# tm8_chinese.net
KiCad netlist of a schematic drawn in EAGLE
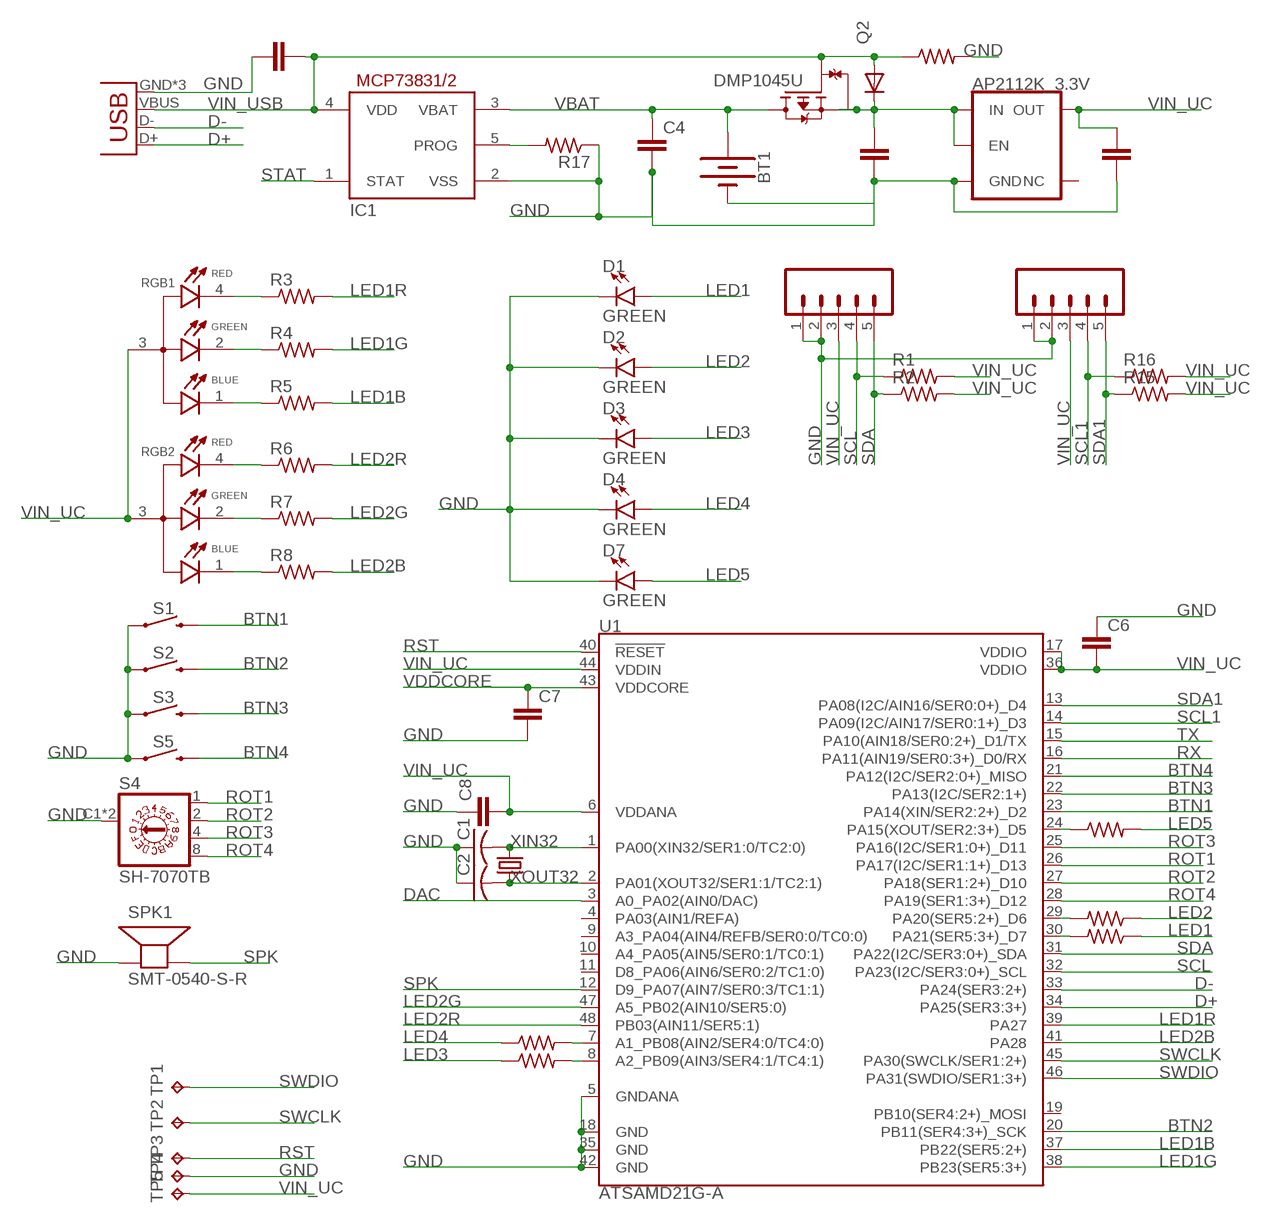
[diagram p0: schematic, sheet 1]

(export (version "E")
  (design (tool "Eeschema 10.0.6"))
  (components
    (comp (ref "AP2112K_3.3V")
      (value "3.3V")
      (footprint "eagle-import:SOT23-5")
      (libsource (lib "eagle-import") (part "V_REG_AP2112K-3.3V"))
    )
    (comp (ref "BT1")
      (value "BATTERY-20MM_SMD_4LEGS_OVERPASTE_INNER")
      (footprint "eagle-import:BATTCON_20MM_4LEGS_OVERPASTE_INNER")
      (libsource (lib "eagle-import") (part "BATTERY-20MM_SMD_4LEGS_OVERPASTE_INNER"))
    )
    (comp (ref "C1")
      (value "C-USC0603")
      (footprint "eagle-import:C0603")
      (libsource (lib "eagle-import") (part "C-USC0603"))
    )
    (comp (ref "C2")
      (value "C-USC0603")
      (footprint "eagle-import:C0603")
      (libsource (lib "eagle-import") (part "C-USC0603"))
    )
    (comp (ref "C3")
      (value "C-EUC0603")
      (footprint "eagle-import:C0603")
      (libsource (lib "eagle-import") (part "C-EUC0603"))
    )
    (comp (ref "C4")
      (value "C-EUC0603")
      (footprint "eagle-import:C0603")
      (libsource (lib "eagle-import") (part "C-EUC0603"))
    )
    (comp (ref "C5")
      (value "C-EUC0603")
      (footprint "eagle-import:C0603")
      (libsource (lib "eagle-import") (part "C-EUC0603"))
    )
    (comp (ref "C6")
      (value "C-EUC0603")
      (footprint "eagle-import:C0603")
      (libsource (lib "eagle-import") (part "C-EUC0603"))
    )
    (comp (ref "C7")
      (value "C-EUC0603")
      (footprint "eagle-import:C0603")
      (libsource (lib "eagle-import") (part "C-EUC0603"))
    )
    (comp (ref "C8")
      (value "C-EUC0603")
      (footprint "eagle-import:C0603")
      (libsource (lib "eagle-import") (part "C-EUC0603"))
    )
    (comp (ref "C9")
      (value "C-EUC0603")
      (footprint "eagle-import:C0603")
      (libsource (lib "eagle-import") (part "C-EUC0603"))
    )
    (comp (ref "D1")
      (value "GREEN")
      (footprint "eagle-import:LED-1206")
      (libsource (lib "eagle-import") (part "LED-GREEN1206"))
    )
    (comp (ref "D2")
      (value "GREEN")
      (footprint "eagle-import:LED-1206")
      (libsource (lib "eagle-import") (part "LED-GREEN1206"))
    )
    (comp (ref "D3")
      (value "GREEN")
      (footprint "eagle-import:LED-1206")
      (libsource (lib "eagle-import") (part "LED-GREEN1206"))
    )
    (comp (ref "D4")
      (value "GREEN")
      (footprint "eagle-import:LED-1206")
      (libsource (lib "eagle-import") (part "LED-GREEN1206"))
    )
    (comp (ref "D7")
      (value "GREEN")
      (footprint "eagle-import:LED-1206")
      (libsource (lib "eagle-import") (part "LED-GREEN1206"))
    )
    (comp (ref "D8")
      (value "DIODESOD-323F")
      (footprint "eagle-import:SOD-323F")
      (libsource (lib "eagle-import") (part "DIODESOD-323F"))
    )
    (comp (ref "IC1")
      (value "MCP73831/OT")
      (footprint "eagle-import:SOT23-5L")
      (libsource (lib "eagle-import") (part "MCP73831/OT"))
    )
    (comp (ref "JP2")
      (value "USB-MICROB")
      (footprint "eagle-import:USB-MICROB")
      (libsource (lib "eagle-import") (part "USB-MICROB"))
    )
    (comp (ref "LCD1")
      (value "CONN_05VERT_FEMALE_HEADER")
      (footprint "eagle-import:1X05_SMD_VERTICAL_COMBO")
      (libsource (lib "eagle-import") (part "CONN_05VERT_FEMALE_HEADER"))
    )
    (comp (ref "LCD2")
      (value "CONN_05VERT_FEMALE_HEADER")
      (footprint "eagle-import:1X05_SMD_VERTICAL_COMBO")
      (libsource (lib "eagle-import") (part "CONN_05VERT_FEMALE_HEADER"))
    )
    (comp (ref "Q2")
      (value "DMP1045U")
      (footprint "eagle-import:SOT91P240X110-3N")
      (fields (field (name "MF") "Diodes Inc."))
      (libsource (lib "eagle-import") (part "DMP1045U"))
    )
    (comp (ref "R1")
      (value "R-US_R0603")
      (footprint "eagle-import:R0603")
      (libsource (lib "eagle-import") (part "rcl_334_R-US_R0603"))
    )
    (comp (ref "R2")
      (value "R-US_R0603")
      (footprint "eagle-import:R0603")
      (libsource (lib "eagle-import") (part "rcl_334_R-US_R0603"))
    )
    (comp (ref "R3")
      (value "R-US_R0603")
      (footprint "eagle-import:R0603")
      (libsource (lib "eagle-import") (part "rcl_334_R-US_R0603"))
    )
    (comp (ref "R4")
      (value "R-US_R0603")
      (footprint "eagle-import:R0603")
      (libsource (lib "eagle-import") (part "rcl_334_R-US_R0603"))
    )
    (comp (ref "R5")
      (value "R-US_R0603")
      (footprint "eagle-import:R0603")
      (libsource (lib "eagle-import") (part "rcl_334_R-US_R0603"))
    )
    (comp (ref "R6")
      (value "R-US_R0603")
      (footprint "eagle-import:R0603")
      (libsource (lib "eagle-import") (part "rcl_334_R-US_R0603"))
    )
    (comp (ref "R7")
      (value "R-US_R0603")
      (footprint "eagle-import:R0603")
      (libsource (lib "eagle-import") (part "rcl_334_R-US_R0603"))
    )
    (comp (ref "R8")
      (value "R-US_R0603")
      (footprint "eagle-import:R0603")
      (libsource (lib "eagle-import") (part "rcl_334_R-US_R0603"))
    )
    (comp (ref "R9")
      (value "R-US_R0603")
      (footprint "eagle-import:R0603")
      (libsource (lib "eagle-import") (part "rcl_334_R-US_R0603"))
    )
    (comp (ref "R10")
      (value "R-US_R0603")
      (footprint "eagle-import:R0603")
      (libsource (lib "eagle-import") (part "rcl_334_R-US_R0603"))
    )
    (comp (ref "R11")
      (value "R-US_R0603")
      (footprint "eagle-import:R0603")
      (libsource (lib "eagle-import") (part "rcl_334_R-US_R0603"))
    )
    (comp (ref "R12")
      (value "R-US_R0603")
      (footprint "eagle-import:R0603")
      (libsource (lib "eagle-import") (part "rcl_334_R-US_R0603"))
    )
    (comp (ref "R13")
      (value "R-US_R0603")
      (footprint "eagle-import:R0603")
      (libsource (lib "eagle-import") (part "rcl_334_R-US_R0603"))
    )
    (comp (ref "R14")
      (value "R-US_R0603")
      (footprint "eagle-import:R0603")
      (libsource (lib "eagle-import") (part "R-US_R0603"))
    )
    (comp (ref "R15")
      (value "R-US_R0603")
      (footprint "eagle-import:R0603")
      (libsource (lib "eagle-import") (part "rcl_334_R-US_R0603"))
    )
    (comp (ref "R16")
      (value "R-US_R0603")
      (footprint "eagle-import:R0603")
      (libsource (lib "eagle-import") (part "rcl_334_R-US_R0603"))
    )
    (comp (ref "R17")
      (value "R-US_R0603")
      (footprint "eagle-import:R0603")
      (libsource (lib "eagle-import") (part "adafruit_25768682_R-US_R0603"))
    )
    (comp (ref "RGB1")
      (value "EAST1616RGBA3")
      (footprint "eagle-import:LED_EAST1616RGBA3")
      (fields (field (name "MF") "Everlight Electronics"))
      (libsource (lib "eagle-import") (part "EAST1616RGBA3"))
    )
    (comp (ref "RGB2")
      (value "EAST1616RGBA3")
      (footprint "eagle-import:LED_EAST1616RGBA3")
      (fields (field (name "MF") "Everlight Electronics"))
      (libsource (lib "eagle-import") (part "EAST1616RGBA3"))
    )
    (comp (ref "S1")
      (value "MOMENTARY-SWITCH-SPST-SMD-6.0X3.5MM")
      (footprint "eagle-import:TACTILE_SWITCH_SMD_6.0X3.5MM")
      (libsource (lib "eagle-import") (part "MOMENTARY-SWITCH-SPST-SMD-6.0X3.5MM"))
    )
    (comp (ref "S2")
      (value "MOMENTARY-SWITCH-SPST-SMD-6.0X3.5MM")
      (footprint "eagle-import:TACTILE_SWITCH_SMD_6.0X3.5MM")
      (libsource (lib "eagle-import") (part "MOMENTARY-SWITCH-SPST-SMD-6.0X3.5MM"))
    )
    (comp (ref "S3")
      (value "MOMENTARY-SWITCH-SPST-SMD-6.0X3.5MM")
      (footprint "eagle-import:TACTILE_SWITCH_SMD_6.0X3.5MM")
      (libsource (lib "eagle-import") (part "MOMENTARY-SWITCH-SPST-SMD-6.0X3.5MM"))
    )
    (comp (ref "S4")
      (value "SH-7070TB")
      (footprint "eagle-import:SH-7070B")
      (fields (field (name "MF") "Nidec Copal"))
      (libsource (lib "eagle-import") (part "SH-7070TB"))
    )
    (comp (ref "S5")
      (value "MOMENTARY-SWITCH-SPST-SMD-6.0X3.5MM")
      (footprint "eagle-import:TACTILE_SWITCH_SMD_6.0X3.5MM")
      (libsource (lib "eagle-import") (part "MOMENTARY-SWITCH-SPST-SMD-6.0X3.5MM"))
    )
    (comp (ref "SPK1")
      (value "SMT-0540-S-R")
      (footprint "eagle-import:SMT-0540-S-R")
      (fields (field (name "MF") "PUI"))
      (libsource (lib "eagle-import") (part "SMT-0540-S-R"))
    )
    (comp (ref "TP1")
      (value "TPTP10R")
      (footprint "eagle-import:TP10R")
      (libsource (lib "eagle-import") (part "TPTP10R"))
    )
    (comp (ref "TP2")
      (value "TPTP10R")
      (footprint "eagle-import:TP10R")
      (libsource (lib "eagle-import") (part "TPTP10R"))
    )
    (comp (ref "TP3")
      (value "TPTP10R")
      (footprint "eagle-import:TP10R")
      (libsource (lib "eagle-import") (part "TPTP10R"))
    )
    (comp (ref "TP4")
      (value "TPTP10R")
      (footprint "eagle-import:TP10R")
      (libsource (lib "eagle-import") (part "TPTP10R"))
    )
    (comp (ref "TP5")
      (value "TPTP10R")
      (footprint "eagle-import:TP10R")
      (libsource (lib "eagle-import") (part "TPTP10R"))
    )
    (comp (ref "U1")
      (value "ATSAMD21G-A")
      (footprint "eagle-import:TQFP-48")
      (libsource (lib "eagle-import") (part "ATSAMD21G-A"))
    )
    (comp (ref "Y1")
      (value "32.768kHz")
      (footprint "eagle-import:CRYSTAL-SMD-3.2X1.5MM")
      (libsource (lib "eagle-import") (part "CRYSTAL-32.768KHZSMD-3.2X1.5"))
    )
  )
  (nets
    (net (code "1") (name "/BTN1") (class "Default")
      (node (ref "S1") (pin "2") (pinfunction "2_2") (pintype "passive"))
      (node (ref "U1") (pin "23") (pinfunction "PA14(XIN/SER2:2+)_D2_23") (pintype "bidirectional"))
    )
    (net (code "2") (name "/BTN2") (class "Default")
      (node (ref "S2") (pin "2") (pinfunction "2_2") (pintype "passive"))
      (node (ref "U1") (pin "20") (pinfunction "PB11(SER4:3+)_SCK_20") (pintype "bidirectional"))
    )
    (net (code "3") (name "/BTN3") (class "Default")
      (node (ref "S3") (pin "2") (pinfunction "2_2") (pintype "passive"))
      (node (ref "U1") (pin "22") (pinfunction "PA13(I2C/SER2:1+)_22") (pintype "bidirectional"))
    )
    (net (code "4") (name "/BTN4") (class "Default")
      (node (ref "S5") (pin "2") (pinfunction "2_2") (pintype "passive"))
      (node (ref "U1") (pin "21") (pinfunction "PA12(I2C/SER2:0+)_MISO_21") (pintype "bidirectional"))
    )
    (net (code "5") (name "/D+") (class "Default")
      (node (ref "JP2") (pin "D+") (pinfunction "D+_D+") (pintype "bidirectional"))
      (node (ref "U1") (pin "34") (pinfunction "PA25(SER3:3+)_34") (pintype "bidirectional"))
    )
    (net (code "6") (name "/D-") (class "Default")
      (node (ref "JP2") (pin "D-") (pinfunction "D-_D-") (pintype "bidirectional"))
      (node (ref "U1") (pin "33") (pinfunction "PA24(SER3:2+)_33") (pintype "bidirectional"))
    )
    (net (code "7") (name "/DAC") (class "Default")
      (node (ref "U1") (pin "3") (pinfunction "A0_PA02(AIN0/DAC)_3") (pintype "bidirectional"))
    )
    (net (code "8") (name "/GND") (class "Default")
      (node (ref "AP2112K_3.3V") (pin "2") (pinfunction "GND_2") (pintype "input"))
      (node (ref "BT1") (pin "2") (pinfunction "-_2") (pintype "power_in"))
      (node (ref "C1") (pin "1") (pinfunction "1_1") (pintype "passive"))
      (node (ref "C2") (pin "1") (pinfunction "1_1") (pintype "passive"))
      (node (ref "C3") (pin "1") (pinfunction "1_1") (pintype "passive"))
      (node (ref "C4") (pin "2") (pinfunction "2_2") (pintype "passive"))
      (node (ref "C5") (pin "2") (pinfunction "2_2") (pintype "passive"))
      (node (ref "C6") (pin "1") (pinfunction "1_1") (pintype "passive"))
      (node (ref "C7") (pin "2") (pinfunction "2_2") (pintype "passive"))
      (node (ref "C8") (pin "1") (pinfunction "1_1") (pintype "passive"))
      (node (ref "C9") (pin "2") (pinfunction "2_2") (pintype "passive"))
      (node (ref "D1") (pin "C") (pinfunction "C_C") (pintype "passive"))
      (node (ref "D2") (pin "C") (pinfunction "C_C") (pintype "passive"))
      (node (ref "D3") (pin "C") (pinfunction "C_C") (pintype "passive"))
      (node (ref "D4") (pin "C") (pinfunction "C_C") (pintype "passive"))
      (node (ref "D7") (pin "C") (pinfunction "C_C") (pintype "passive"))
      (node (ref "IC1") (pin "2") (pinfunction "VSS_2") (pintype "power_in"))
      (node (ref "JP2") (pin "GND") (pinfunction "GND_GND") (pintype "bidirectional"))
      (node (ref "JP2") (pin "MT1") (pinfunction "GND_MT1") (pintype "bidirectional"))
      (node (ref "JP2") (pin "MT2") (pinfunction "GND_MT2") (pintype "bidirectional"))
      (node (ref "LCD1") (pin "1") (pinfunction "1_1") (pintype "passive"))
      (node (ref "LCD1") (pin "2") (pinfunction "2_2") (pintype "passive"))
      (node (ref "LCD2") (pin "1") (pinfunction "1_1") (pintype "passive"))
      (node (ref "LCD2") (pin "2") (pinfunction "2_2") (pintype "passive"))
      (node (ref "R14") (pin "2") (pinfunction "2_2") (pintype "passive"))
      (node (ref "R17") (pin "1") (pinfunction "1_1") (pintype "passive"))
      (node (ref "S1") (pin "1") (pinfunction "1_1") (pintype "passive"))
      (node (ref "S2") (pin "1") (pinfunction "1_1") (pintype "passive"))
      (node (ref "S3") (pin "1") (pinfunction "1_1") (pintype "passive"))
      (node (ref "S4") (pin "C1") (pinfunction "C_C1") (pintype "passive"))
      (node (ref "S4") (pin "C2") (pinfunction "C_C2") (pintype "passive"))
      (node (ref "S5") (pin "1") (pinfunction "1_1") (pintype "passive"))
      (node (ref "SPK1") (pin "-") (pinfunction "+_-") (pintype "passive"))
      (node (ref "TP4") (pin "TP") (pinfunction "TP_TP") (pintype "input"))
      (node (ref "U1") (pin "18") (pinfunction "GND_18") (pintype "bidirectional"))
      (node (ref "U1") (pin "35") (pinfunction "GND_35") (pintype "bidirectional"))
      (node (ref "U1") (pin "42") (pinfunction "GND_42") (pintype "bidirectional"))
      (node (ref "U1") (pin "5") (pinfunction "GNDANA_5") (pintype "bidirectional"))
    )
    (net (code "9") (name "/LED1") (class "Default")
      (node (ref "D1") (pin "A") (pinfunction "A_A") (pintype "passive"))
      (node (ref "R9") (pin "1") (pinfunction "1_1") (pintype "passive"))
    )
    (net (code "10") (name "/LED1B") (class "Default")
      (node (ref "R5") (pin "2") (pinfunction "2_2") (pintype "passive"))
      (node (ref "U1") (pin "37") (pinfunction "PB22(SER5:2+)_37") (pintype "bidirectional"))
    )
    (net (code "11") (name "/LED1G") (class "Default")
      (node (ref "R4") (pin "2") (pinfunction "2_2") (pintype "passive"))
      (node (ref "U1") (pin "38") (pinfunction "PB23(SER5:3+)_38") (pintype "bidirectional"))
    )
    (net (code "12") (name "/LED1R") (class "Default")
      (node (ref "R3") (pin "2") (pinfunction "2_2") (pintype "passive"))
      (node (ref "U1") (pin "39") (pinfunction "PA27_39") (pintype "bidirectional"))
    )
    (net (code "13") (name "/LED2") (class "Default")
      (node (ref "D2") (pin "A") (pinfunction "A_A") (pintype "passive"))
      (node (ref "R10") (pin "1") (pinfunction "1_1") (pintype "passive"))
    )
    (net (code "14") (name "/LED2B") (class "Default")
      (node (ref "R8") (pin "2") (pinfunction "2_2") (pintype "passive"))
      (node (ref "U1") (pin "41") (pinfunction "PA28_41") (pintype "bidirectional"))
    )
    (net (code "15") (name "/LED2G") (class "Default")
      (node (ref "R7") (pin "2") (pinfunction "2_2") (pintype "passive"))
      (node (ref "U1") (pin "47") (pinfunction "A5_PB02(AIN10/SER5:0)_47") (pintype "bidirectional"))
    )
    (net (code "16") (name "/LED2R") (class "Default")
      (node (ref "R6") (pin "2") (pinfunction "2_2") (pintype "passive"))
      (node (ref "U1") (pin "48") (pinfunction "PB03(AIN11/SER5:1)_48") (pintype "bidirectional"))
    )
    (net (code "17") (name "/LED3") (class "Default")
      (node (ref "D3") (pin "A") (pinfunction "A_A") (pintype "passive"))
      (node (ref "R11") (pin "1") (pinfunction "1_1") (pintype "passive"))
    )
    (net (code "18") (name "/LED4") (class "Default")
      (node (ref "D4") (pin "A") (pinfunction "A_A") (pintype "passive"))
      (node (ref "R12") (pin "1") (pinfunction "1_1") (pintype "passive"))
    )
    (net (code "19") (name "/LED5") (class "Default")
      (node (ref "D7") (pin "A") (pinfunction "A_A") (pintype "passive"))
      (node (ref "R13") (pin "2") (pinfunction "2_2") (pintype "passive"))
    )
    (net (code "20") (name "/ROT1") (class "Default")
      (node (ref "S4") (pin "1") (pinfunction "1_1") (pintype "passive"))
      (node (ref "U1") (pin "26") (pinfunction "PA17(I2C/SER1:1+)_D13_26") (pintype "bidirectional"))
    )
    (net (code "21") (name "/ROT2") (class "Default")
      (node (ref "S4") (pin "2") (pinfunction "2_2") (pintype "passive"))
      (node (ref "U1") (pin "27") (pinfunction "PA18(SER1:2+)_D10_27") (pintype "bidirectional"))
    )
    (net (code "22") (name "/ROT3") (class "Default")
      (node (ref "S4") (pin "4") (pinfunction "4_4") (pintype "passive"))
      (node (ref "U1") (pin "25") (pinfunction "PA16(I2C/SER1:0+)_D11_25") (pintype "bidirectional"))
    )
    (net (code "23") (name "/ROT4") (class "Default")
      (node (ref "S4") (pin "8") (pinfunction "8_8") (pintype "passive"))
      (node (ref "U1") (pin "28") (pinfunction "PA19(SER1:3+)_D12_28") (pintype "bidirectional"))
    )
    (net (code "24") (name "/RST") (class "Default")
      (node (ref "TP3") (pin "TP") (pinfunction "TP_TP") (pintype "input"))
      (node (ref "U1") (pin "40") (pinfunction "~{RESET}_40") (pintype "bidirectional"))
    )
    (net (code "25") (name "/RX") (class "Default")
      (node (ref "U1") (pin "16") (pinfunction "PA11(AIN19/SER0:3+)_D0/RX_16") (pintype "bidirectional"))
    )
    (net (code "26") (name "/SCL") (class "Default")
      (node (ref "LCD1") (pin "4") (pinfunction "4_4") (pintype "passive"))
      (node (ref "R1") (pin "1") (pinfunction "1_1") (pintype "passive"))
      (node (ref "U1") (pin "32") (pinfunction "PA23(I2C/SER3:0+)_SCL_32") (pintype "bidirectional"))
    )
    (net (code "27") (name "/SCL1") (class "Default")
      (node (ref "LCD2") (pin "4") (pinfunction "4_4") (pintype "passive"))
      (node (ref "R16") (pin "1") (pinfunction "1_1") (pintype "passive"))
      (node (ref "U1") (pin "14") (pinfunction "PA09(I2C/AIN17/SER0:1+)_D3_14") (pintype "bidirectional"))
    )
    (net (code "28") (name "/SDA") (class "Default")
      (node (ref "LCD1") (pin "5") (pinfunction "5_5") (pintype "passive"))
      (node (ref "R2") (pin "1") (pinfunction "1_1") (pintype "passive"))
      (node (ref "U1") (pin "31") (pinfunction "PA22(I2C/SER3:0+)_SDA_31") (pintype "bidirectional"))
    )
    (net (code "29") (name "/SDA1") (class "Default")
      (node (ref "LCD2") (pin "5") (pinfunction "5_5") (pintype "passive"))
      (node (ref "R15") (pin "1") (pinfunction "1_1") (pintype "passive"))
      (node (ref "U1") (pin "13") (pinfunction "PA08(I2C/AIN16/SER0:0+)_D4_13") (pintype "bidirectional"))
    )
    (net (code "30") (name "/SPK") (class "Default")
      (node (ref "SPK1") (pin "+") (pinfunction "-_+") (pintype "passive"))
      (node (ref "U1") (pin "12") (pinfunction "D9_PA07(AIN7/SER0:3/TC1:1)_12") (pintype "bidirectional"))
    )
    (net (code "31") (name "/STAT") (class "Default")
      (node (ref "IC1") (pin "1") (pinfunction "STAT_1") (pintype "output"))
    )
    (net (code "32") (name "/SWCLK") (class "Default")
      (node (ref "TP2") (pin "TP") (pinfunction "TP_TP") (pintype "input"))
      (node (ref "U1") (pin "45") (pinfunction "PA30(SWCLK/SER1:2+)_45") (pintype "bidirectional"))
    )
    (net (code "33") (name "/SWDIO") (class "Default")
      (node (ref "TP1") (pin "TP") (pinfunction "TP_TP") (pintype "input"))
      (node (ref "U1") (pin "46") (pinfunction "PA31(SWDIO/SER1:3+)_46") (pintype "bidirectional"))
    )
    (net (code "34") (name "/TX") (class "Default")
      (node (ref "U1") (pin "15") (pinfunction "PA10(AIN18/SER0:2+)_D1/TX_15") (pintype "bidirectional"))
    )
    (net (code "35") (name "/VBAT") (class "Default")
      (node (ref "BT1") (pin "1") (pinfunction "+_1") (pintype "power_in"))
      (node (ref "C4") (pin "1") (pinfunction "1_1") (pintype "passive"))
      (node (ref "IC1") (pin "3") (pinfunction "VBAT_3") (pintype "bidirectional"))
      (node (ref "Q2") (pin "3") (pinfunction "D_3") (pintype "passive"))
    )
    (net (code "36") (name "/VDDCORE") (class "Default")
      (node (ref "C7") (pin "1") (pinfunction "1_1") (pintype "passive"))
      (node (ref "U1") (pin "43") (pinfunction "VDDCORE_43") (pintype "bidirectional"))
    )
    (net (code "37") (name "/VIN_UC") (class "Default")
      (node (ref "AP2112K_3.3V") (pin "5") (pinfunction "OUT_5") (pintype "passive"))
      (node (ref "C5") (pin "1") (pinfunction "1_1") (pintype "passive"))
      (node (ref "C6") (pin "2") (pinfunction "2_2") (pintype "passive"))
      (node (ref "C8") (pin "2") (pinfunction "2_2") (pintype "passive"))
      (node (ref "LCD1") (pin "3") (pinfunction "3_3") (pintype "passive"))
      (node (ref "LCD2") (pin "3") (pinfunction "3_3") (pintype "passive"))
      (node (ref "R1") (pin "2") (pinfunction "2_2") (pintype "passive"))
      (node (ref "R15") (pin "2") (pinfunction "2_2") (pintype "passive"))
      (node (ref "R16") (pin "2") (pinfunction "2_2") (pintype "passive"))
      (node (ref "R2") (pin "2") (pinfunction "2_2") (pintype "passive"))
      (node (ref "RGB1") (pin "3") (pinfunction "A_3") (pintype "passive"))
      (node (ref "RGB2") (pin "3") (pinfunction "A_3") (pintype "passive"))
      (node (ref "TP5") (pin "TP") (pinfunction "TP_TP") (pintype "input"))
      (node (ref "U1") (pin "17") (pinfunction "VDDIO_17") (pintype "bidirectional"))
      (node (ref "U1") (pin "36") (pinfunction "VDDIO_36") (pintype "bidirectional"))
      (node (ref "U1") (pin "44") (pinfunction "VDDIN_44") (pintype "bidirectional"))
      (node (ref "U1") (pin "6") (pinfunction "VDDANA_6") (pintype "bidirectional"))
    )
    (net (code "38") (name "/VIN_USB") (class "Default")
      (node (ref "C3") (pin "2") (pinfunction "2_2") (pintype "passive"))
      (node (ref "D8") (pin "A") (pinfunction "A_A") (pintype "passive"))
      (node (ref "IC1") (pin "4") (pinfunction "VDD_4") (pintype "power_in"))
      (node (ref "JP2") (pin "VBUS") (pinfunction "VBUS_VBUS") (pintype "bidirectional"))
      (node (ref "Q2") (pin "1") (pinfunction "G_1") (pintype "passive"))
      (node (ref "R14") (pin "1") (pinfunction "1_1") (pintype "passive"))
    )
    (net (code "39") (name "/XIN32") (class "Default")
      (node (ref "C1") (pin "2") (pinfunction "2_2") (pintype "passive"))
      (node (ref "U1") (pin "1") (pinfunction "PA00(XIN32/SER1:0/TC2:0)_1") (pintype "bidirectional"))
      (node (ref "Y1") (pin "P$2") (pinfunction "2_P$2") (pintype "passive"))
    )
    (net (code "40") (name "/XOUT32") (class "Default")
      (node (ref "C2") (pin "2") (pinfunction "2_2") (pintype "passive"))
      (node (ref "U1") (pin "2") (pinfunction "PA01(XOUT32/SER1:1/TC2:1)_2") (pintype "bidirectional"))
      (node (ref "Y1") (pin "P$1") (pinfunction "1_P$1") (pintype "passive"))
    )
    (net (code "41") (name "Net-(AP2112K_3.3V-EN)") (class "Default")
      (node (ref "AP2112K_3.3V") (pin "1") (pinfunction "IN_1") (pintype "input"))
      (node (ref "AP2112K_3.3V") (pin "3") (pinfunction "EN_3") (pintype "input"))
      (node (ref "C9") (pin "1") (pinfunction "1_1") (pintype "passive"))
      (node (ref "D8") (pin "C") (pinfunction "C_C") (pintype "passive"))
      (node (ref "Q2") (pin "2") (pinfunction "S_2") (pintype "passive"))
    )
    (net (code "42") (name "Net-(IC1-PROG)") (class "Default")
      (node (ref "IC1") (pin "5") (pinfunction "PROG_5") (pintype "input"))
      (node (ref "R17") (pin "2") (pinfunction "2_2") (pintype "passive"))
    )
    (net (code "43") (name "Net-(RGB1-B_C)") (class "Default")
      (node (ref "R5") (pin "1") (pinfunction "1_1") (pintype "passive"))
      (node (ref "RGB1") (pin "1") (pinfunction "B_C_1") (pintype "passive"))
    )
    (net (code "44") (name "Net-(RGB1-G_C)") (class "Default")
      (node (ref "R4") (pin "1") (pinfunction "1_1") (pintype "passive"))
      (node (ref "RGB1") (pin "2") (pinfunction "G_C_2") (pintype "passive"))
    )
    (net (code "45") (name "Net-(RGB1-R_C)") (class "Default")
      (node (ref "R3") (pin "1") (pinfunction "1_1") (pintype "passive"))
      (node (ref "RGB1") (pin "4") (pinfunction "R_C_4") (pintype "passive"))
    )
    (net (code "46") (name "Net-(RGB2-B_C)") (class "Default")
      (node (ref "R8") (pin "1") (pinfunction "1_1") (pintype "passive"))
      (node (ref "RGB2") (pin "1") (pinfunction "B_C_1") (pintype "passive"))
    )
    (net (code "47") (name "Net-(RGB2-G_C)") (class "Default")
      (node (ref "R7") (pin "1") (pinfunction "1_1") (pintype "passive"))
      (node (ref "RGB2") (pin "2") (pinfunction "G_C_2") (pintype "passive"))
    )
    (net (code "48") (name "Net-(RGB2-R_C)") (class "Default")
      (node (ref "R6") (pin "1") (pinfunction "1_1") (pintype "passive"))
      (node (ref "RGB2") (pin "4") (pinfunction "R_C_4") (pintype "passive"))
    )
    (net (code "49") (name "Net-(U1-A1_PB08(AIN2{slash}SER4:0{slash}TC4:0))") (class "Default")
      (node (ref "R12") (pin "2") (pinfunction "2_2") (pintype "passive"))
      (node (ref "U1") (pin "7") (pinfunction "A1_PB08(AIN2/SER4:0/TC4:0)_7") (pintype "bidirectional"))
    )
    (net (code "50") (name "Net-(U1-A2_PB09(AIN3{slash}SER4:1{slash}TC4:1))") (class "Default")
      (node (ref "R11") (pin "2") (pinfunction "2_2") (pintype "passive"))
      (node (ref "U1") (pin "8") (pinfunction "A2_PB09(AIN3/SER4:1/TC4:1)_8") (pintype "bidirectional"))
    )
    (net (code "51") (name "Net-(U1-PA15(XOUT{slash}SER2:3+)_D5)") (class "Default")
      (node (ref "R13") (pin "1") (pinfunction "1_1") (pintype "passive"))
      (node (ref "U1") (pin "24") (pinfunction "PA15(XOUT/SER2:3+)_D5_24") (pintype "bidirectional"))
    )
    (net (code "52") (name "Net-(U1-PA20(SER5:2+)_D6)") (class "Default")
      (node (ref "R10") (pin "2") (pinfunction "2_2") (pintype "passive"))
      (node (ref "U1") (pin "29") (pinfunction "PA20(SER5:2+)_D6_29") (pintype "bidirectional"))
    )
    (net (code "53") (name "Net-(U1-PA21(SER5:3+)_D7)") (class "Default")
      (node (ref "R9") (pin "2") (pinfunction "2_2") (pintype "passive"))
      (node (ref "U1") (pin "30") (pinfunction "PA21(SER5:3+)_D7_30") (pintype "bidirectional"))
    )
    (net (code "54") (name "unconnected-(AP2112K_3.3V-NC-Pad4)") (class "Default")
      (node (ref "AP2112K_3.3V") (pin "4") (pinfunction "NC_4") (pintype "no_connect"))
    )
    (net (code "55") (name "unconnected-(U1-A3_PA04(AIN4{slash}REFB{slash}SER0:0{slash}TC0:0)-Pad9)") (class "Default")
      (node (ref "U1") (pin "9") (pinfunction "A3_PA04(AIN4/REFB/SER0:0/TC0:0)_9") (pintype "bidirectional"))
    )
    (net (code "56") (name "unconnected-(U1-A4_PA05(AIN5{slash}SER0:1{slash}TC0:1)-Pad10)") (class "Default")
      (node (ref "U1") (pin "10") (pinfunction "A4_PA05(AIN5/SER0:1/TC0:1)_10") (pintype "bidirectional"))
    )
    (net (code "57") (name "unconnected-(U1-D8_PA06(AIN6{slash}SER0:2{slash}TC1:0)-Pad11)") (class "Default")
      (node (ref "U1") (pin "11") (pinfunction "D8_PA06(AIN6/SER0:2/TC1:0)_11") (pintype "bidirectional"))
    )
    (net (code "58") (name "unconnected-(U1-PA03(AIN1{slash}REFA)-Pad4)") (class "Default")
      (node (ref "U1") (pin "4") (pinfunction "PA03(AIN1/REFA)_4") (pintype "bidirectional"))
    )
    (net (code "59") (name "unconnected-(U1-PB10(SER4:2+)_MOSI-Pad19)") (class "Default")
      (node (ref "U1") (pin "19") (pinfunction "PB10(SER4:2+)_MOSI_19") (pintype "bidirectional"))
    )
  )
)
